# beVimPowerBoard.net
KiCad netlist of a schematic drawn in EAGLE
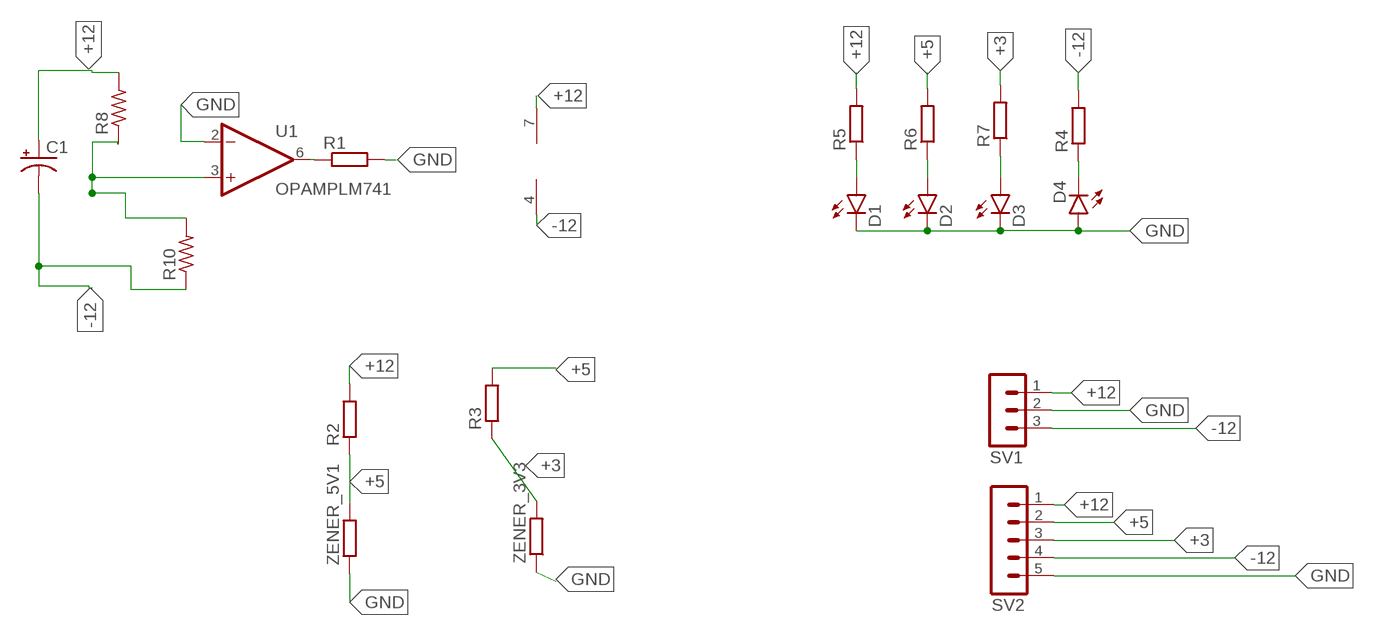
[diagram p0: schematic, sheet 1]

(export (version "E")
  (design (tool "Eeschema 10.0.6"))
  (components
    (comp (ref "C1")
      (value "CAPACITOR-POLARIZEDRADIAL-POLARIZED-6.3MM-TANTALUM")
      (footprint "eagle-import:RADIAL-POLARIZED-6.3MM-TANTALUM")
      (libsource (lib "eagle-import") (part "CAPACITOR-POLARIZEDRADIAL-POLARIZED-6.3MM-TANTALUM"))
    )
    (comp (ref "D1")
      (value "LED5MM")
      (footprint "eagle-import:LED5MM")
      (libsource (lib "eagle-import") (part "LED5MM"))
    )
    (comp (ref "D2")
      (value "LED5MM")
      (footprint "eagle-import:LED5MM")
      (libsource (lib "eagle-import") (part "LED5MM"))
    )
    (comp (ref "D3")
      (value "LED5MM")
      (footprint "eagle-import:LED5MM")
      (libsource (lib "eagle-import") (part "LED5MM"))
    )
    (comp (ref "D4")
      (value "LED5MM")
      (footprint "eagle-import:LED5MM")
      (libsource (lib "eagle-import") (part "LED5MM"))
    )
    (comp (ref "R1")
      (value "R-EU_0817/7V")
      (footprint "eagle-import:P0817V")
      (libsource (lib "eagle-import") (part "R-EU_0817/7V"))
    )
    (comp (ref "R2")
      (value "R-EU_0817/7V")
      (footprint "eagle-import:P0817V")
      (libsource (lib "eagle-import") (part "R-EU_0817/7V"))
    )
    (comp (ref "R3")
      (value "R-EU_0817/7V")
      (footprint "eagle-import:P0817V")
      (libsource (lib "eagle-import") (part "R-EU_0817/7V"))
    )
    (comp (ref "R4")
      (value "R-EU_0817/7V")
      (footprint "eagle-import:P0817V")
      (libsource (lib "eagle-import") (part "R-EU_0817/7V"))
    )
    (comp (ref "R5")
      (value "R-EU_0817/7V")
      (footprint "eagle-import:P0817V")
      (libsource (lib "eagle-import") (part "R-EU_0817/7V"))
    )
    (comp (ref "R6")
      (value "R-EU_0817/7V")
      (footprint "eagle-import:P0817V")
      (libsource (lib "eagle-import") (part "R-EU_0817/7V"))
    )
    (comp (ref "R7")
      (value "R-EU_0817/7V")
      (footprint "eagle-import:P0817V")
      (libsource (lib "eagle-import") (part "R-EU_0817/7V"))
    )
    (comp (ref "R8")
      (value "R-US_0309/12")
      (footprint "eagle-import:0309_12")
      (libsource (lib "eagle-import") (part "R-US_0309/12"))
    )
    (comp (ref "R10")
      (value "R-US_0309/12")
      (footprint "eagle-import:0309_12")
      (libsource (lib "eagle-import") (part "R-US_0309/12"))
    )
    (comp (ref "SV1")
      (value "MA03-1")
      (footprint "eagle-import:MA03-1")
      (libsource (lib "eagle-import") (part "MA03-1"))
    )
    (comp (ref "SV2")
      (value "MA05-1")
      (footprint "eagle-import:MA05-1")
      (libsource (lib "eagle-import") (part "MA05-1"))
    )
    (comp (ref "U1")
      (value "OPAMPLM741")
      (footprint "eagle-import:DIP8")
      (libsource (lib "eagle-import") (part "OPAMPLM741"))
    )
    (comp (ref "ZENER_3V3")
      (value "R-EU_0817/7V")
      (footprint "eagle-import:P0817V")
      (libsource (lib "eagle-import") (part "R-EU_0817/7V"))
    )
    (comp (ref "ZENER_5V1")
      (value "R-EU_0817/7V")
      (footprint "eagle-import:P0817V")
      (libsource (lib "eagle-import") (part "R-EU_0817/7V"))
    )
  )
  (nets
    (net (code "1") (name "+3") (class "Default")
      (node (ref "R3") (pin "1") (pinfunction "1_1") (pintype "passive"))
      (node (ref "R7") (pin "2") (pinfunction "2_2") (pintype "passive"))
      (node (ref "SV2") (pin "3") (pinfunction "3_3") (pintype "passive"))
      (node (ref "ZENER_3V3") (pin "2") (pinfunction "2_2") (pintype "passive"))
    )
    (net (code "2") (name "+5") (class "Default")
      (node (ref "R2") (pin "1") (pinfunction "1_1") (pintype "passive"))
      (node (ref "R3") (pin "2") (pinfunction "2_2") (pintype "passive"))
      (node (ref "R6") (pin "2") (pinfunction "2_2") (pintype "passive"))
      (node (ref "SV2") (pin "2") (pinfunction "2_2") (pintype "passive"))
      (node (ref "ZENER_5V1") (pin "2") (pinfunction "2_2") (pintype "passive"))
    )
    (net (code "3") (name "+12") (class "Default")
      (node (ref "C1") (pin "+") (pinfunction "+_+") (pintype "passive"))
      (node (ref "R2") (pin "2") (pinfunction "2_2") (pintype "passive"))
      (node (ref "R5") (pin "2") (pinfunction "2_2") (pintype "passive"))
      (node (ref "R8") (pin "2") (pinfunction "2_2") (pintype "passive"))
      (node (ref "SV1") (pin "1") (pinfunction "1_1") (pintype "passive"))
      (node (ref "SV2") (pin "1") (pinfunction "1_1") (pintype "passive"))
      (node (ref "U1") (pin "7") (pinfunction "VCC_7") (pintype "power_in"))
    )
    (net (code "4") (name "-12") (class "Default")
      (node (ref "C1") (pin "-") (pinfunction "-_-") (pintype "passive"))
      (node (ref "R10") (pin "1") (pinfunction "1_1") (pintype "passive"))
      (node (ref "R4") (pin "2") (pinfunction "2_2") (pintype "passive"))
      (node (ref "SV1") (pin "3") (pinfunction "3_3") (pintype "passive"))
      (node (ref "SV2") (pin "4") (pinfunction "4_4") (pintype "passive"))
      (node (ref "U1") (pin "4") (pinfunction "VEE_4") (pintype "power_in"))
    )
    (net (code "5") (name "GND") (class "Default")
      (node (ref "D1") (pin "K") (pinfunction "C_K") (pintype "passive"))
      (node (ref "D2") (pin "K") (pinfunction "C_K") (pintype "passive"))
      (node (ref "D3") (pin "K") (pinfunction "C_K") (pintype "passive"))
      (node (ref "D4") (pin "A") (pinfunction "A_A") (pintype "passive"))
      (node (ref "R1") (pin "2") (pinfunction "2_2") (pintype "passive"))
      (node (ref "SV1") (pin "2") (pinfunction "2_2") (pintype "passive"))
      (node (ref "SV2") (pin "5") (pinfunction "5_5") (pintype "passive"))
      (node (ref "U1") (pin "2") (pinfunction "IN-_2") (pintype "input"))
      (node (ref "ZENER_3V3") (pin "1") (pinfunction "1_1") (pintype "passive"))
      (node (ref "ZENER_5V1") (pin "1") (pinfunction "1_1") (pintype "passive"))
    )
    (net (code "6") (name "Net-(D1-PadA)") (class "Default")
      (node (ref "D1") (pin "A") (pinfunction "A_A") (pintype "passive"))
      (node (ref "R5") (pin "1") (pinfunction "1_1") (pintype "passive"))
    )
    (net (code "7") (name "Net-(D2-PadA)") (class "Default")
      (node (ref "D2") (pin "A") (pinfunction "A_A") (pintype "passive"))
      (node (ref "R6") (pin "1") (pinfunction "1_1") (pintype "passive"))
    )
    (net (code "8") (name "Net-(D3-PadA)") (class "Default")
      (node (ref "D3") (pin "A") (pinfunction "A_A") (pintype "passive"))
      (node (ref "R7") (pin "1") (pinfunction "1_1") (pintype "passive"))
    )
    (net (code "9") (name "Net-(D4-C)") (class "Default")
      (node (ref "D4") (pin "K") (pinfunction "C_K") (pintype "passive"))
      (node (ref "R4") (pin "1") (pinfunction "1_1") (pintype "passive"))
    )
    (net (code "10") (name "Net-(U1A-IN+)") (class "Default")
      (node (ref "R10") (pin "2") (pinfunction "2_2") (pintype "passive"))
      (node (ref "R8") (pin "1") (pinfunction "1_1") (pintype "passive"))
      (node (ref "U1") (pin "3") (pinfunction "IN+_3") (pintype "input"))
    )
    (net (code "11") (name "Net-(U1A-OUT)") (class "Default")
      (node (ref "R1") (pin "1") (pinfunction "1_1") (pintype "passive"))
      (node (ref "U1") (pin "6") (pinfunction "OUT_6") (pintype "output"))
    )
  )
)
